# 11A-005.net
KiCad netlist of a schematic drawn in EAGLE
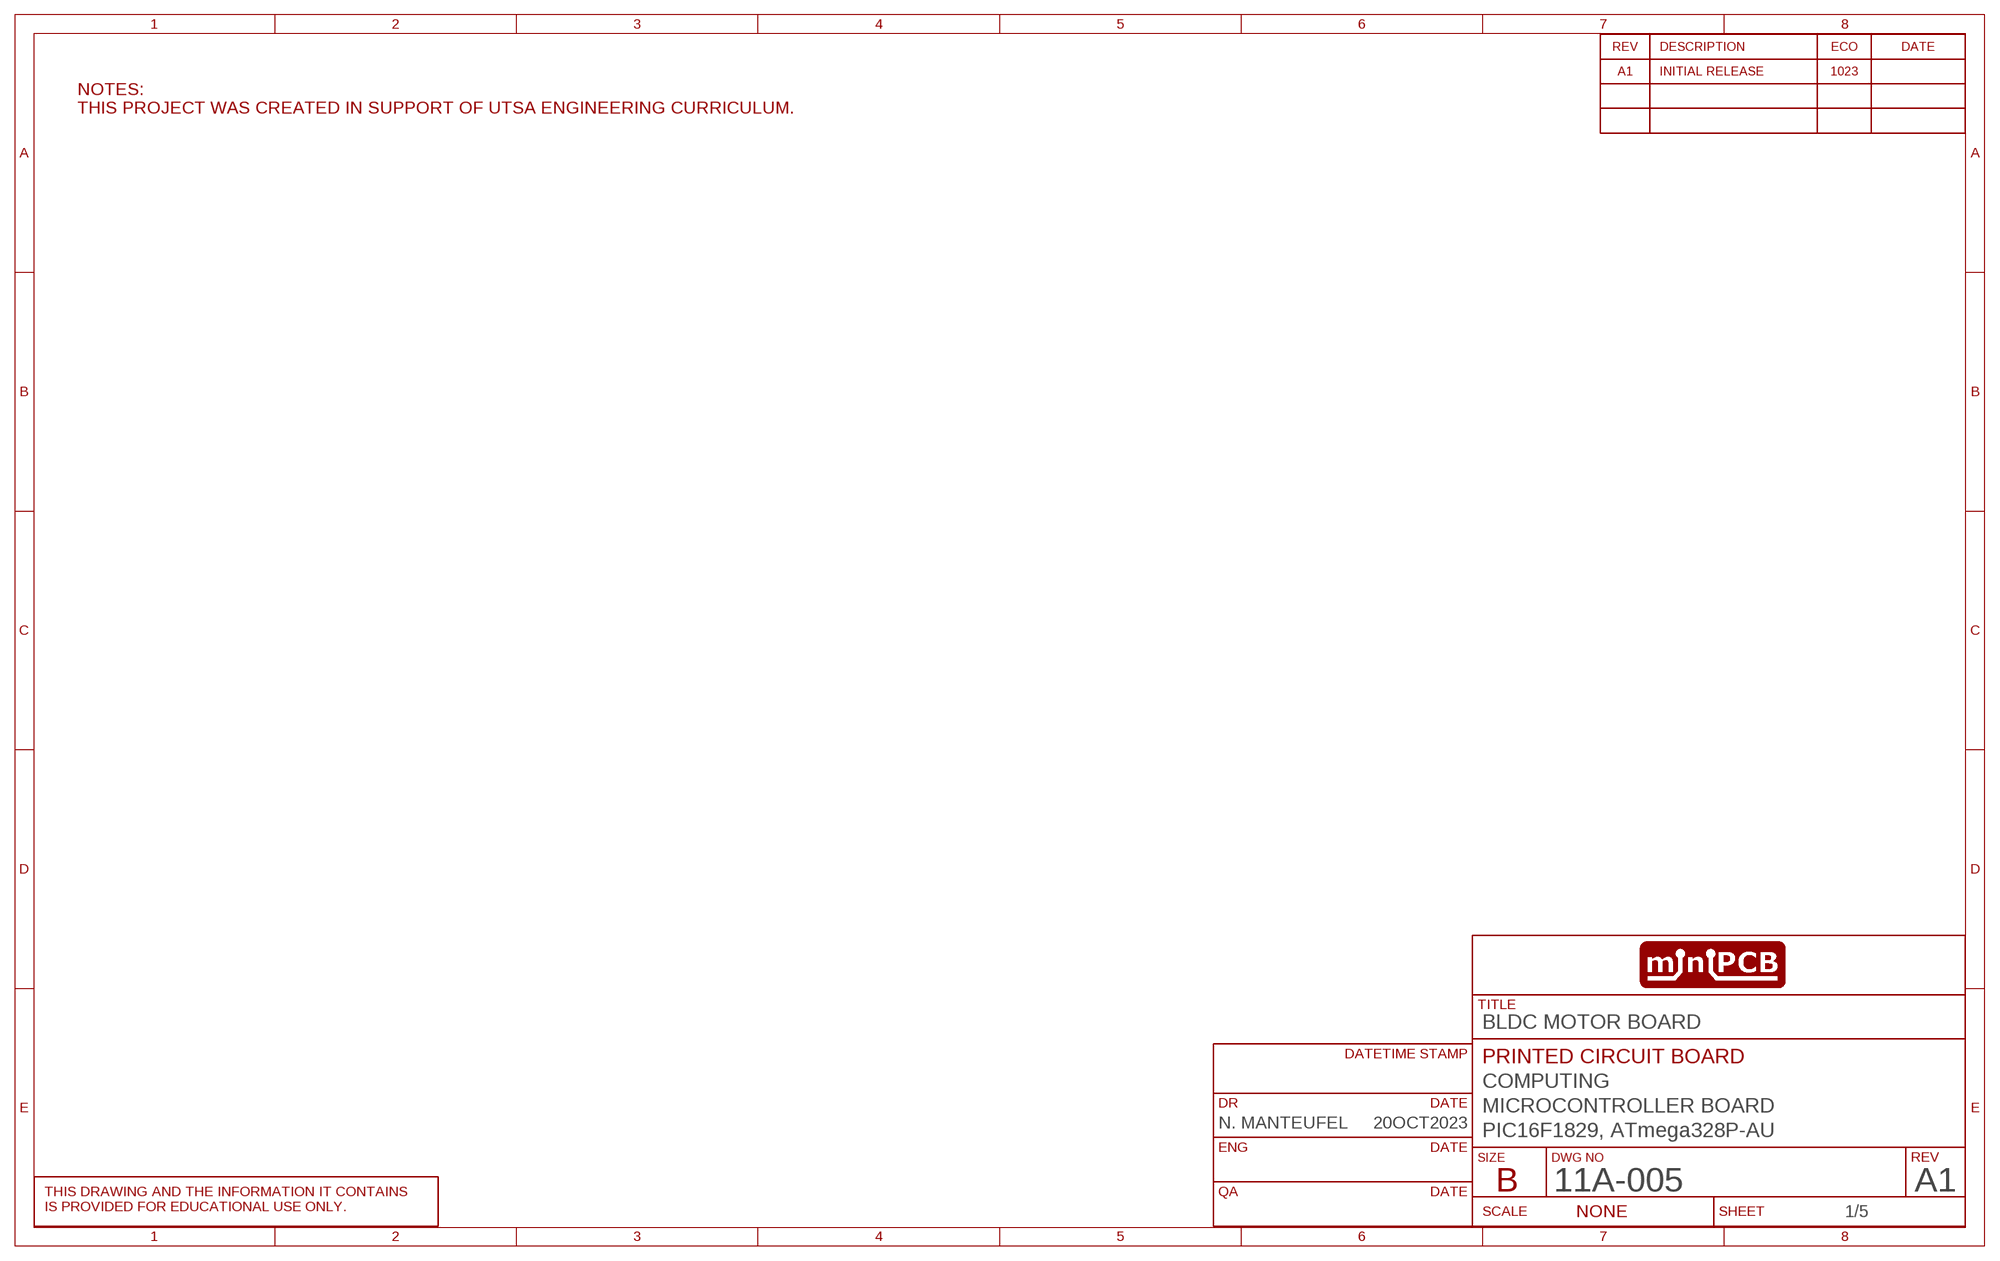
[diagram p0: schematic, sheet 1]
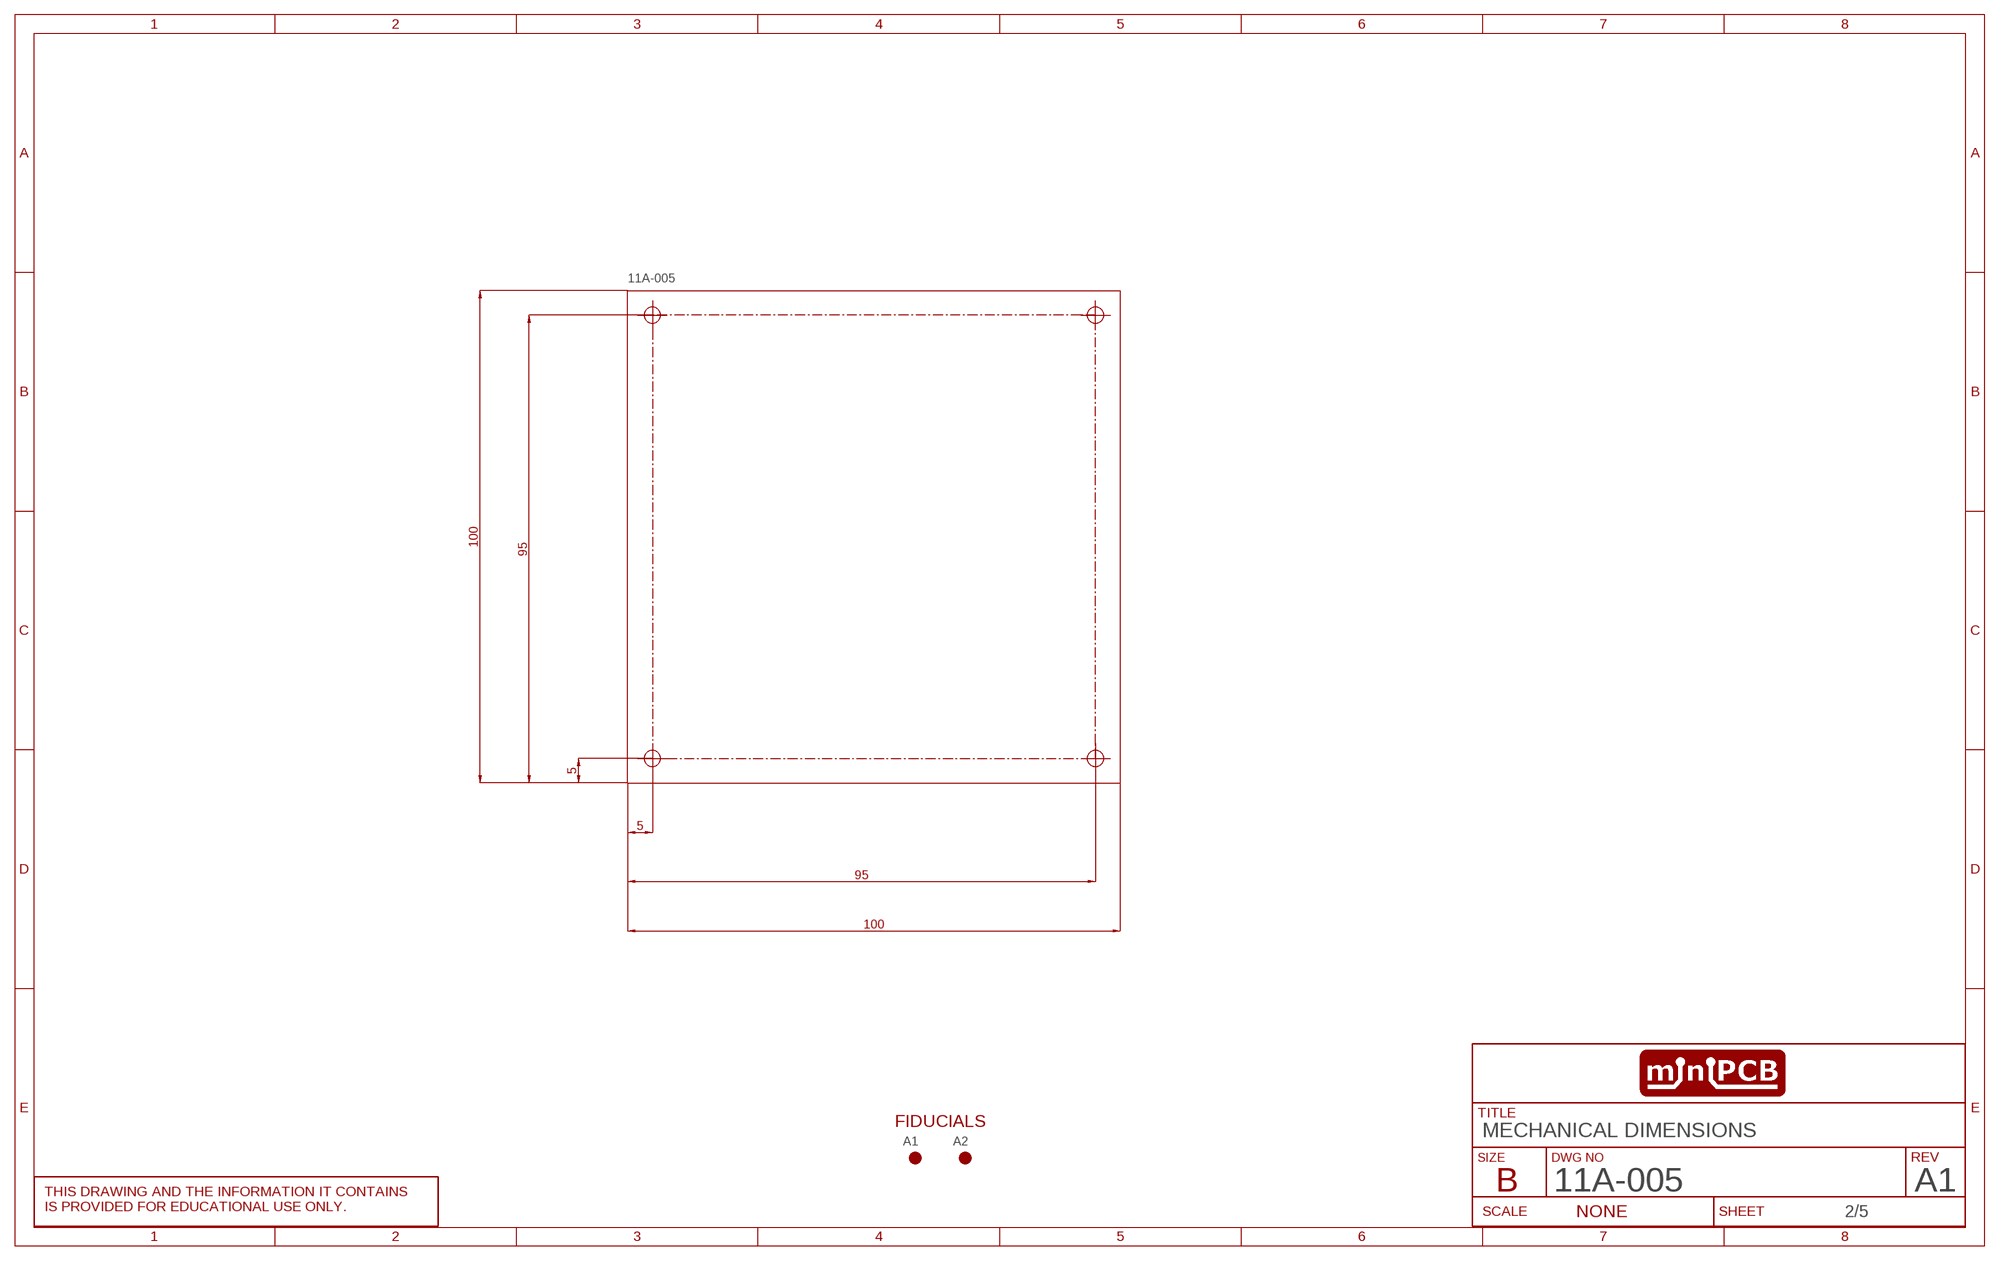
[diagram p1: schematic, sheet 2]
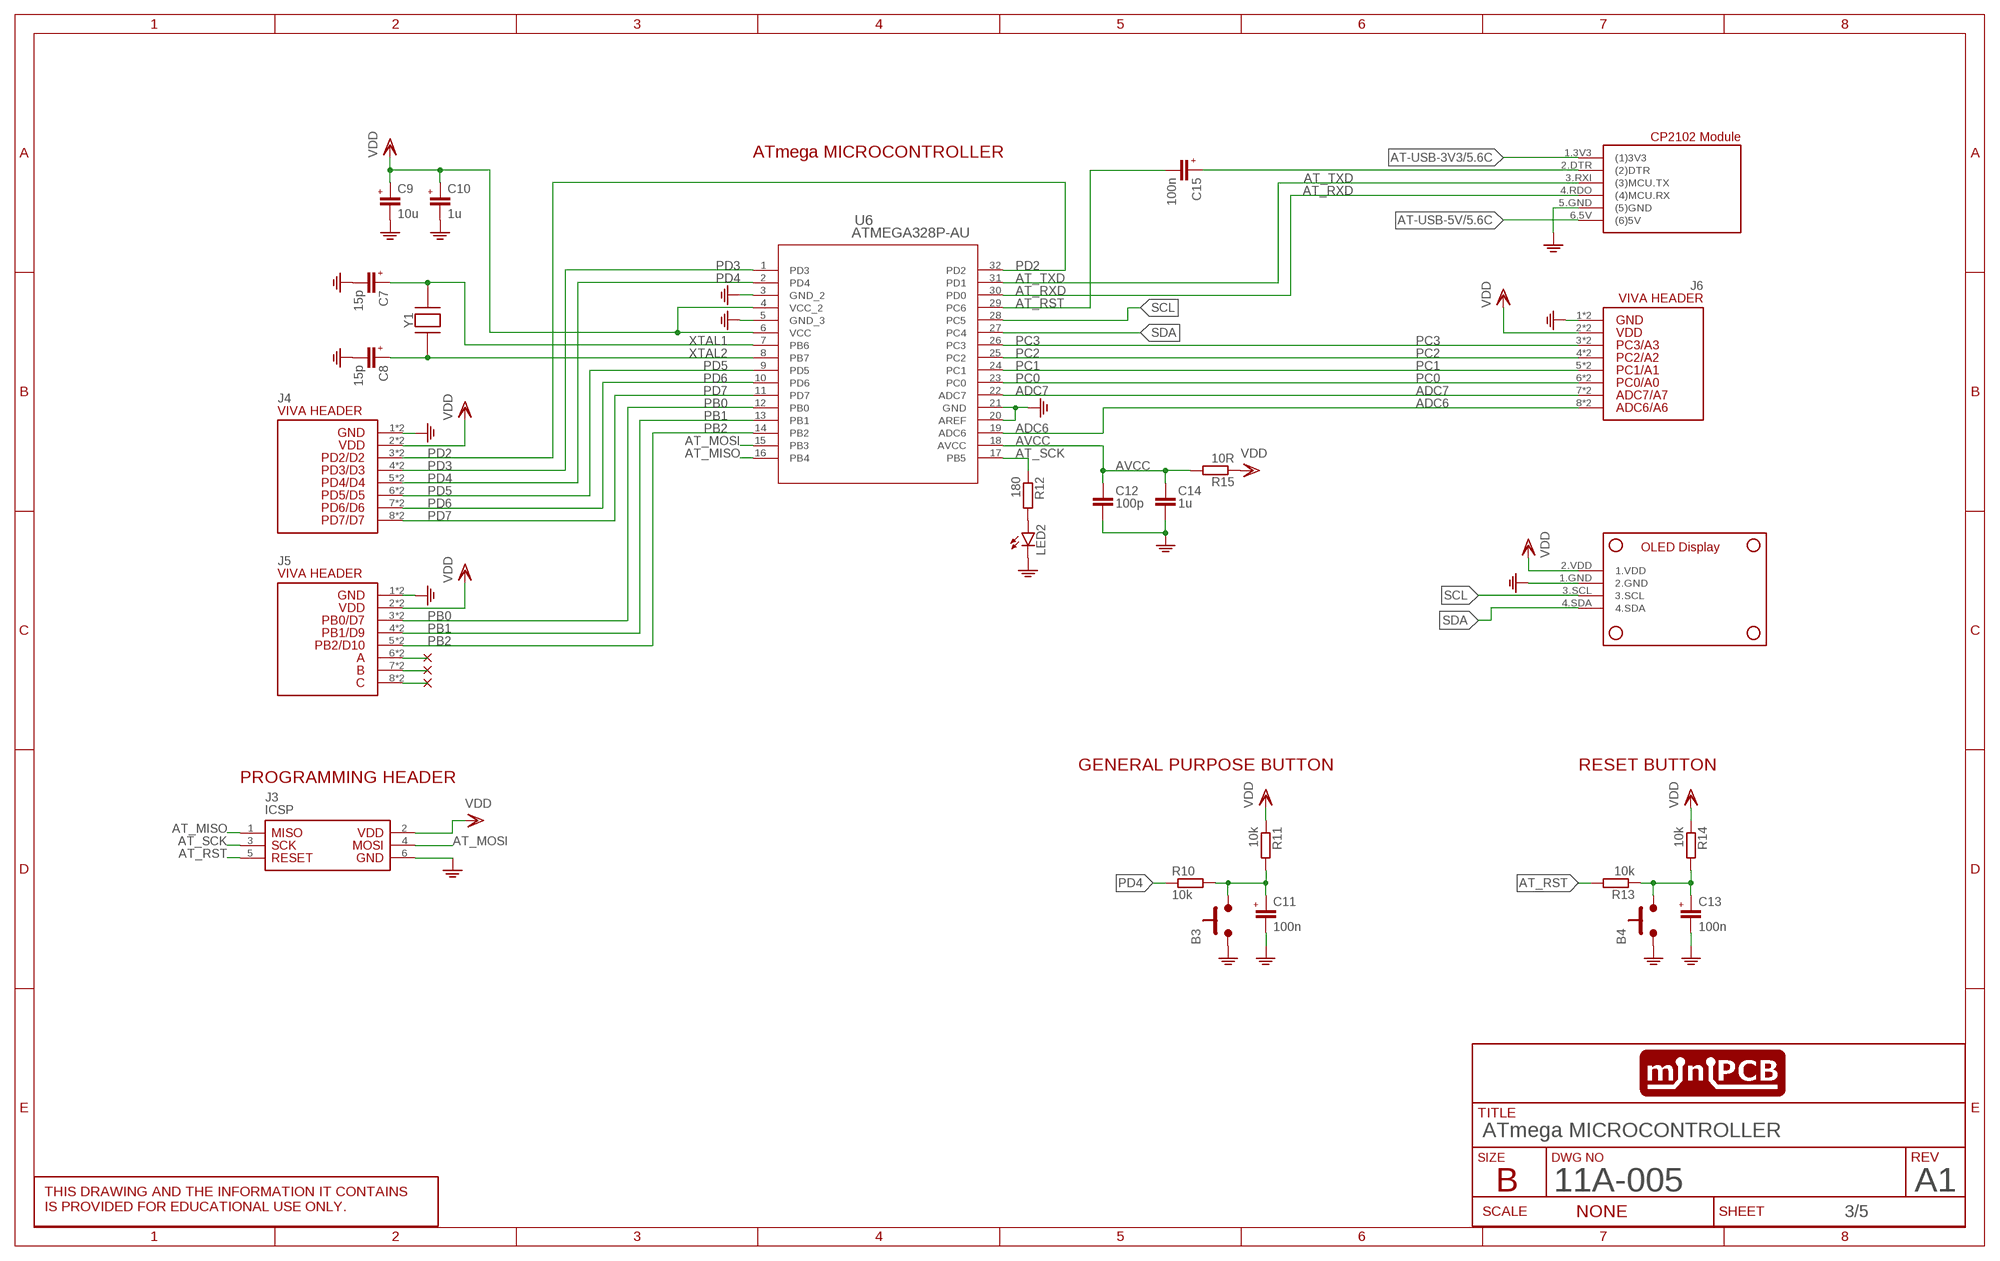
[diagram p2: schematic, sheet 3]
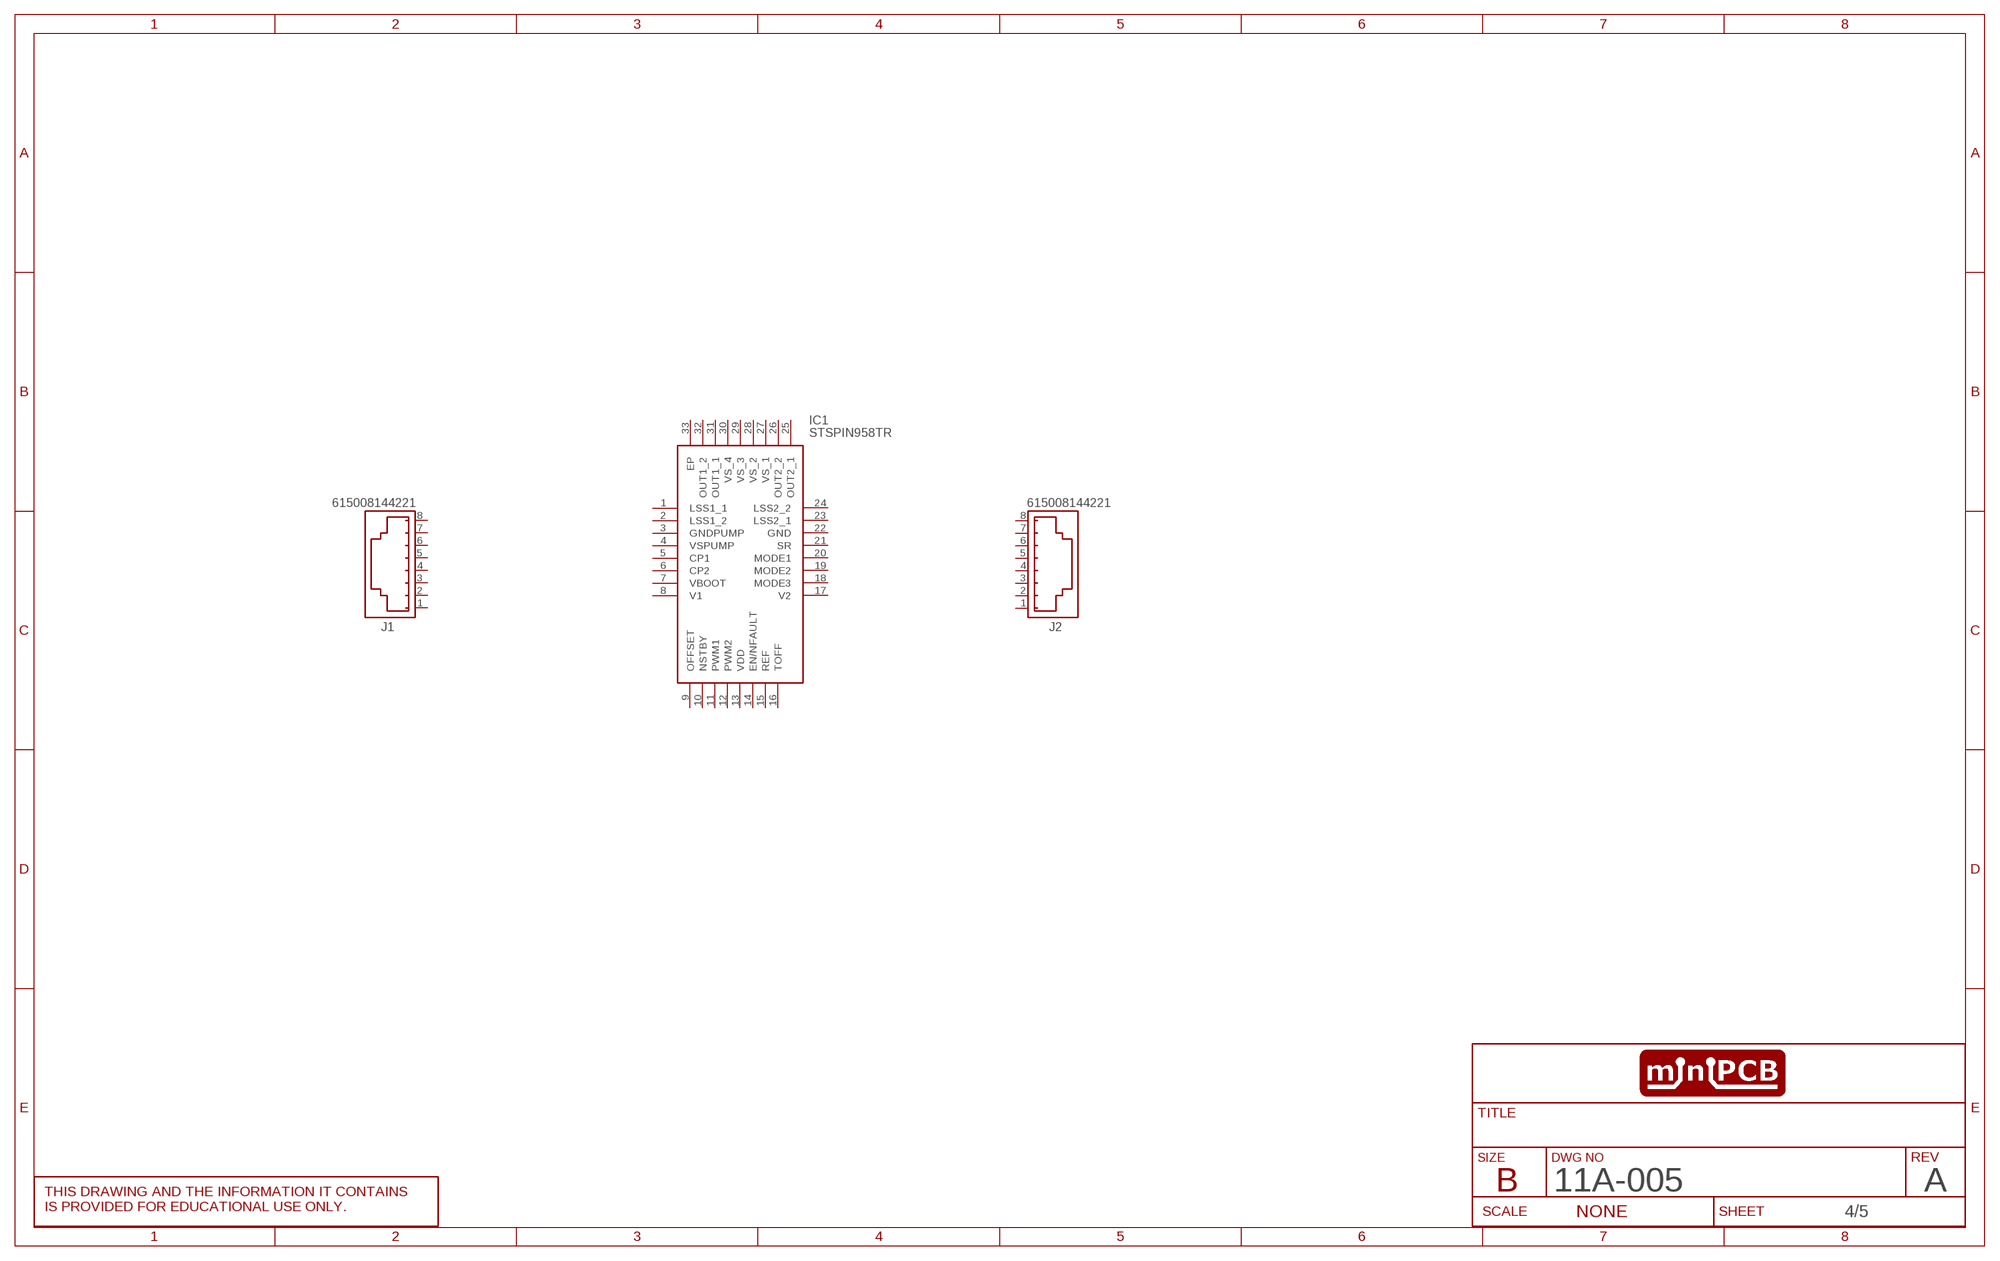
[diagram p3: schematic, sheet 4]
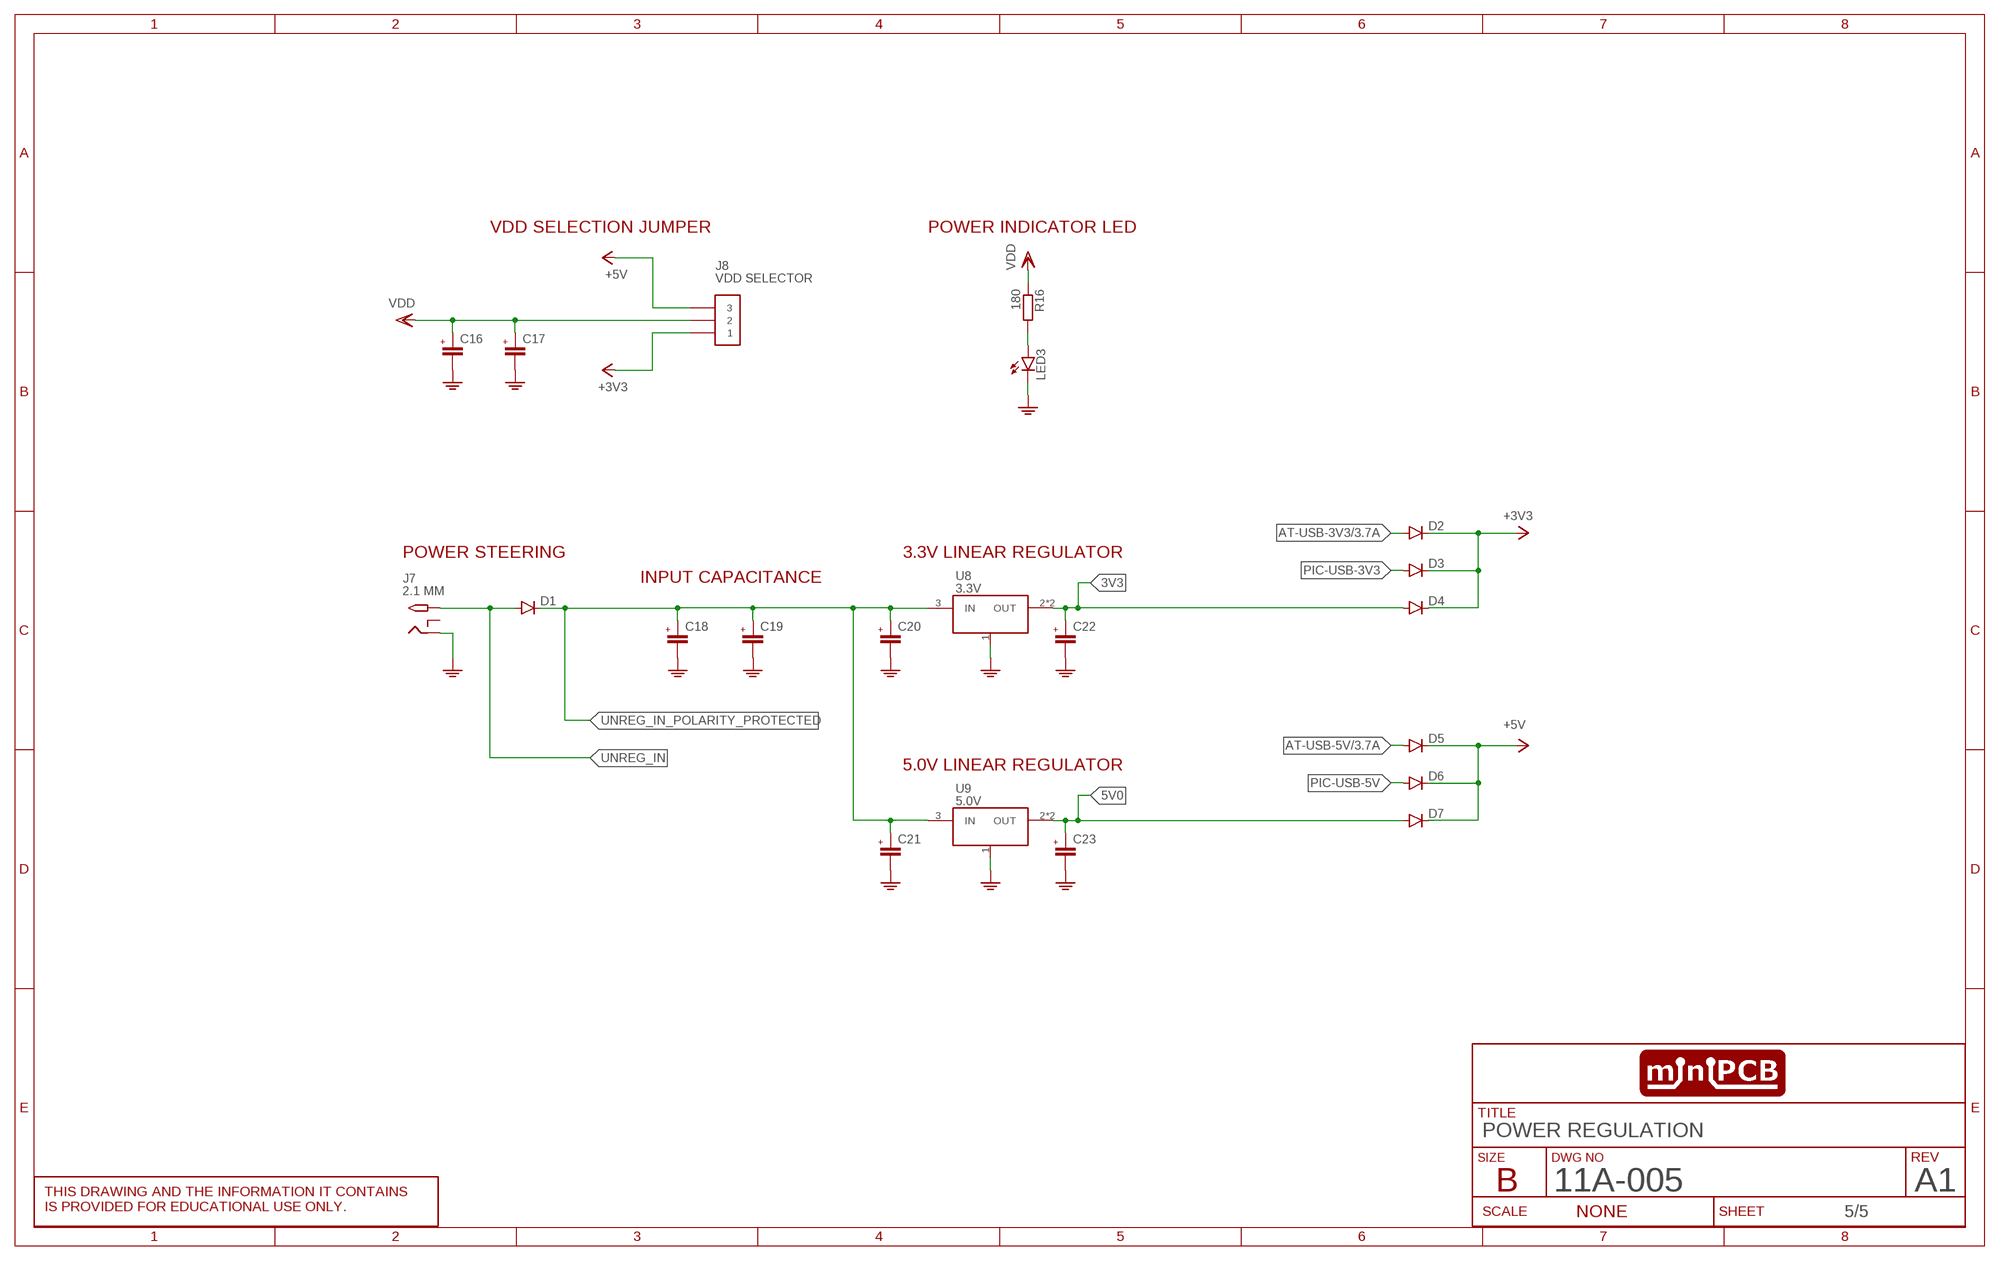
[diagram p4: schematic, sheet 5]

(export (version "E")
  (design (tool "Eeschema 10.0.6"))
  (components
    (comp (ref "IC1")
      (value "STSPIN958TR")
      (footprint "eagle-import:QFN50P500X500X100-33N")
      (fields (field (name "MOUSER_PART_NUMBER") "511-STSPIN958TR"))
      (libsource (lib "eagle-import") (part "STSPIN958TR"))
    )
    (comp (ref "J1")
      (value "615008144221")
      (footprint "eagle-import:615008144221")
      (libsource (lib "eagle-import") (part "615008144221"))
    )
    (comp (ref "J2")
      (value "615008144221")
      (footprint "eagle-import:615008144221")
      (libsource (lib "eagle-import") (part "615008144221"))
    )
    (comp (ref "$3_73_$")
      (value "VIVA_OLEDGND")
      (footprint "eagle-import:VIVA_OLED-I2C-ALT")
      (libsource (lib "eagle-import") (part "VIVA_OLEDGND"))
    )
    (comp (ref "B3")
      (value "PUSHBUTTON6X6MM")
      (footprint "eagle-import:6X6MM")
      (libsource (lib "eagle-import") (part "PUSHBUTTON6X6MM"))
    )
    (comp (ref "B4")
      (value "PUSHBUTTON6X6MM")
      (footprint "eagle-import:6X6MM")
      (libsource (lib "eagle-import") (part "PUSHBUTTON6X6MM"))
    )
    (comp (ref "C7")
      (value "15p")
      (footprint "eagle-import:C0603")
      (libsource (lib "eagle-import") (part "C0603"))
    )
    (comp (ref "C8")
      (value "15p")
      (footprint "eagle-import:C0603")
      (libsource (lib "eagle-import") (part "C0603"))
    )
    (comp (ref "C9")
      (value "10u")
      (footprint "eagle-import:C0805")
      (libsource (lib "eagle-import") (part "C0805"))
    )
    (comp (ref "C10")
      (value "1u")
      (footprint "eagle-import:C0805")
      (libsource (lib "eagle-import") (part "C0805"))
    )
    (comp (ref "C11")
      (value "100n")
      (footprint "eagle-import:C0805")
      (libsource (lib "eagle-import") (part "C0805"))
    )
    (comp (ref "C12")
      (value "100p")
      (footprint "eagle-import:C0805")
      (libsource (lib "eagle-import") (part "C-EU_C0805"))
    )
    (comp (ref "C13")
      (value "100n")
      (footprint "eagle-import:C0805")
      (libsource (lib "eagle-import") (part "C0805"))
    )
    (comp (ref "C14")
      (value "1u")
      (footprint "eagle-import:C0805")
      (libsource (lib "eagle-import") (part "C-EU_C0805"))
    )
    (comp (ref "C15")
      (value "100n")
      (footprint "eagle-import:C0805")
      (libsource (lib "eagle-import") (part "C0805"))
    )
    (comp (ref "J3")
      (value "ICSP")
      (footprint "eagle-import:PINS_6-2X3_AT")
      (fields
        (field (name "P1") "P1 NAME")
        (field (name "P3") "P3 NAME")
        (field (name "P5") "P5 NAME")
        (field (name "P2") "P2 NAME")
        (field (name "P4") "P4 NAME")
        (field (name "P6") "P6 NAME")
        (field (name "P1_1") "MISO")
        (field (name "P2_1") "VDD")
        (field (name "P3_1") "SCK")
        (field (name "P4_1") "MOSI")
        (field (name "P5_1") "RESET")
        (field (name "P6_1") "GND")
      )
      (libsource (lib "eagle-import") (part "PINS_6-2X3_AT"))
    )
    (comp (ref "J4")
      (value "VIVA-HEADER-ADC-8P")
      (footprint "eagle-import:VIVA-HEADER-ADC-8P")
      (fields
        (field (name "P3") "P3 TEXT")
        (field (name "P4") "P4 TEXT")
        (field (name "P5") "P5 TEXT")
        (field (name "P6") "P6 TEXT")
        (field (name "P7") "P7 TEXT")
        (field (name "P8") "P8 TEXT")
        (field (name "P3_1") "PD2/D2")
        (field (name "P4_1") "PD3/D3")
        (field (name "P5_1") "PD4/D4")
        (field (name "P6_1") "PD5/D5")
        (field (name "P7_1") "PD6/D6")
        (field (name "P8_1") "PD7/D7")
      )
      (libsource (lib "eagle-import") (part "VIVA-HEADER-ADC-8P"))
    )
    (comp (ref "J5")
      (value "VIVA-HEADER-ADC-8P")
      (footprint "eagle-import:VIVA-HEADER-ADC-8P")
      (fields
        (field (name "P3") "P3 TEXT")
        (field (name "P4") "P4 TEXT")
        (field (name "P5") "P5 TEXT")
        (field (name "P6") "P6 TEXT")
        (field (name "P7") "P7 TEXT")
        (field (name "P8") "P8 TEXT")
        (field (name "P3_1") "PB0/D7")
        (field (name "P4_1") "PB1/D9")
        (field (name "P5_1") "PB2/D10")
        (field (name "P6_1") "A")
        (field (name "P7_1") "B")
        (field (name "P8_1") "C")
      )
      (libsource (lib "eagle-import") (part "VIVA-HEADER-ADC-8P"))
    )
    (comp (ref "J6")
      (value "VIVA-HEADER-ADC-8P")
      (footprint "eagle-import:VIVA-HEADER-ADC-8P")
      (fields
        (field (name "P3") "P3 TEXT")
        (field (name "P4") "P4 TEXT")
        (field (name "P5") "P5 TEXT")
        (field (name "P6") "P6 TEXT")
        (field (name "P7") "P7 TEXT")
        (field (name "P8") "P8 TEXT")
        (field (name "P3_1") "PC3/A3")
        (field (name "P4_1") "PC2/A2")
        (field (name "P5_1") "PC1/A1")
        (field (name "P6_1") "PC0/A0")
        (field (name "P7_1") "ADC7/A7")
        (field (name "P8_1") "ADC6/A6")
      )
      (libsource (lib "eagle-import") (part "VIVA-HEADER-ADC-8P"))
    )
    (comp (ref "LED2")
      (value "LEDSML0805")
      (footprint "eagle-import:SML0805")
      (libsource (lib "eagle-import") (part "LEDSML0805"))
    )
    (comp (ref "R10")
      (value "10k")
      (footprint "eagle-import:R0805")
      (libsource (lib "eagle-import") (part "R-EU__R0805"))
    )
    (comp (ref "R11")
      (value "10k")
      (footprint "eagle-import:R0805")
      (libsource (lib "eagle-import") (part "R-EU__R0805"))
    )
    (comp (ref "R12")
      (value "180")
      (footprint "eagle-import:R0805")
      (libsource (lib "eagle-import") (part "R-EU__R0805"))
    )
    (comp (ref "R13")
      (value "10k")
      (footprint "eagle-import:R0805")
      (libsource (lib "eagle-import") (part "R-EU__R0805"))
    )
    (comp (ref "R14")
      (value "10k")
      (footprint "eagle-import:R0805")
      (libsource (lib "eagle-import") (part "R-EU__R0805"))
    )
    (comp (ref "R15")
      (value "10R")
      (footprint "eagle-import:R0805")
      (libsource (lib "eagle-import") (part "R-EU__R0805"))
    )
    (comp (ref "U6")
      (value "ATMEGA328P-AU")
      (footprint "eagle-import:32A_ATM")
      (fields
        (field (name "MANUFACTURER_PART_NUMBER") "ATMEGA328-AU")
        (field (name "COPYRIGHT") "Copyright (C) 2021 Ultra Librarian. All rights reserved.")
      )
      (libsource (lib "eagle-import") (part "ATMEGA328-AU"))
    )
    (comp (ref "U7")
      (value "VIVA_USB-TTL")
      (footprint "eagle-import:VIVA_USB_TTL_SUBTEXT")
      (libsource (lib "eagle-import") (part "VIVA_USB-TTL"))
    )
    (comp (ref "Y1")
      (value "CRYSTAL-3225_4P")
      (footprint "eagle-import:TXC7M2")
      (libsource (lib "eagle-import") (part "CRYSTAL-3225_4P"))
    )
    (comp (ref "-")
      (value "11A-005")
      (footprint "eagle-import:PCB_100X100")
      (libsource (lib "eagle-import") (part "PCB_100X100"))
    )
    (comp (ref "A1")
      (value "FIDUCIAL")
      (footprint "eagle-import:FIDUCIAL")
      (libsource (lib "eagle-import") (part "FIDUCIAL"))
    )
    (comp (ref "A2")
      (value "FIDUCIAL")
      (footprint "eagle-import:FIDUCIAL")
      (libsource (lib "eagle-import") (part "FIDUCIAL"))
    )
    (comp (ref "C16")
      (value "C0805")
      (footprint "eagle-import:C0805")
      (libsource (lib "eagle-import") (part "C0805"))
    )
    (comp (ref "C17")
      (value "C0805")
      (footprint "eagle-import:C0805")
      (libsource (lib "eagle-import") (part "C0805"))
    )
    (comp (ref "C18")
      (value "C0805")
      (footprint "eagle-import:C0805")
      (libsource (lib "eagle-import") (part "C0805"))
    )
    (comp (ref "C19")
      (value "C0805")
      (footprint "eagle-import:C0805")
      (libsource (lib "eagle-import") (part "C0805"))
    )
    (comp (ref "C20")
      (value "C0805")
      (footprint "eagle-import:C0805")
      (libsource (lib "eagle-import") (part "C0805"))
    )
    (comp (ref "C21")
      (value "C0805")
      (footprint "eagle-import:C0805")
      (libsource (lib "eagle-import") (part "C0805"))
    )
    (comp (ref "C22")
      (value "C0805")
      (footprint "eagle-import:C0805")
      (libsource (lib "eagle-import") (part "C0805"))
    )
    (comp (ref "C23")
      (value "C0805")
      (footprint "eagle-import:C0805")
      (libsource (lib "eagle-import") (part "C0805"))
    )
    (comp (ref "D1")
      (value "DIODE-DO214AC")
      (footprint "eagle-import:DO214AC")
      (libsource (lib "eagle-import") (part "DIODE-DO214AC"))
    )
    (comp (ref "D2")
      (value "DIODE-DO214AC")
      (footprint "eagle-import:DO214AC")
      (libsource (lib "eagle-import") (part "DIODE-DO214AC"))
    )
    (comp (ref "D3")
      (value "DIODE-DO214AC")
      (footprint "eagle-import:DO214AC")
      (libsource (lib "eagle-import") (part "DIODE-DO214AC"))
    )
    (comp (ref "D4")
      (value "DIODE-DO214AC")
      (footprint "eagle-import:DO214AC")
      (libsource (lib "eagle-import") (part "DIODE-DO214AC"))
    )
    (comp (ref "D5")
      (value "DIODE-DO214AC")
      (footprint "eagle-import:DO214AC")
      (libsource (lib "eagle-import") (part "DIODE-DO214AC"))
    )
    (comp (ref "D6")
      (value "DIODE-DO214AC")
      (footprint "eagle-import:DO214AC")
      (libsource (lib "eagle-import") (part "DIODE-DO214AC"))
    )
    (comp (ref "D7")
      (value "DIODE-DO214AC")
      (footprint "eagle-import:DO214AC")
      (libsource (lib "eagle-import") (part "DIODE-DO214AC"))
    )
    (comp (ref "J7")
      (value "2.1 MM")
      (footprint "eagle-import:PJ-102A")
      (libsource (lib "eagle-import") (part "2.1MMJACKTHM"))
    )
    (comp (ref "J8")
      (value "VDD SELECTOR")
      (footprint "eagle-import:PINS_3")
      (libsource (lib "eagle-import") (part "PINS_3_2.54"))
    )
    (comp (ref "LED3")
      (value "LEDSML0805")
      (footprint "eagle-import:SML0805")
      (libsource (lib "eagle-import") (part "LEDSML0805"))
    )
    (comp (ref "R16")
      (value "180")
      (footprint "eagle-import:R0805")
      (libsource (lib "eagle-import") (part "R-EU__R0805"))
    )
    (comp (ref "U8")
      (value "3.3V")
      (footprint "eagle-import:SOT223")
      (libsource (lib "eagle-import") (part "REGULATOR_SCHLM1117"))
    )
    (comp (ref "U9")
      (value "5.0V")
      (footprint "eagle-import:SOT223")
      (libsource (lib "eagle-import") (part "REGULATOR_SCHLM1117"))
    )
  )
  (nets
    (net (code "1") (name "+3V3") (class "Default")
      (node (ref "D2") (pin "C") (pinfunction "C_C") (pintype "passive"))
      (node (ref "D3") (pin "C") (pinfunction "C_C") (pintype "passive"))
      (node (ref "D4") (pin "C") (pinfunction "C_C") (pintype "passive"))
      (node (ref "J8") (pin "1") (pinfunction "1_1") (pintype "bidirectional"))
    )
    (net (code "2") (name "+5V") (class "Default")
      (node (ref "D5") (pin "C") (pinfunction "C_C") (pintype "passive"))
      (node (ref "D6") (pin "C") (pinfunction "C_C") (pintype "passive"))
      (node (ref "D7") (pin "C") (pinfunction "C_C") (pintype "passive"))
      (node (ref "J8") (pin "3") (pinfunction "3_3") (pintype "bidirectional"))
    )
    (net (code "3") (name "3V3") (class "Default")
      (node (ref "C22") (pin "1") (pinfunction "+_1") (pintype "passive"))
      (node (ref "D4") (pin "A") (pinfunction "A_A") (pintype "passive"))
      (node (ref "U8") (pin "2") (pinfunction "OUT_2") (pintype "bidirectional"))
      (node (ref "U8") (pin "4.TAB") (pinfunction "OUT_4.TAB") (pintype "bidirectional"))
    )
    (net (code "4") (name "5V0") (class "Default")
      (node (ref "C23") (pin "1") (pinfunction "+_1") (pintype "passive"))
      (node (ref "D7") (pin "A") (pinfunction "A_A") (pintype "passive"))
      (node (ref "U9") (pin "2") (pinfunction "OUT_2") (pintype "bidirectional"))
      (node (ref "U9") (pin "4.TAB") (pinfunction "OUT_4.TAB") (pintype "bidirectional"))
    )
    (net (code "5") (name "ADC6") (class "Default")
      (node (ref "J6") (pin "8") (pinfunction "8.ADC5_8") (pintype "bidirectional"))
      (node (ref "J6") (pin "9") (pinfunction "8.ADC5_9") (pintype "bidirectional"))
      (node (ref "U6") (pin "19") (pinfunction "ADC6_19") (pintype "passive"))
    )
    (net (code "6") (name "ADC7") (class "Default")
      (node (ref "J6") (pin "10") (pinfunction "7.ADC4_10") (pintype "bidirectional"))
      (node (ref "J6") (pin "7") (pinfunction "7.ADC4_7") (pintype "bidirectional"))
      (node (ref "U6") (pin "22") (pinfunction "ADC7_22") (pintype "passive"))
    )
    (net (code "7") (name "AT-USB-3V3") (class "Default")
      (node (ref "D2") (pin "A") (pinfunction "A_A") (pintype "passive"))
      (node (ref "U7") (pin "1.3V3") (pinfunction "(1)3V3_1.3V3") (pintype "bidirectional"))
    )
    (net (code "8") (name "AT-USB-5V") (class "Default")
      (node (ref "D5") (pin "A") (pinfunction "A_A") (pintype "passive"))
      (node (ref "U7") (pin "6.5V") (pinfunction "(6)5V_6.5V") (pintype "bidirectional"))
    )
    (net (code "9") (name "AT_MISO") (class "Default")
      (node (ref "J3") (pin "1") (pinfunction "1_1") (pintype "bidirectional"))
      (node (ref "U6") (pin "16") (pinfunction "PB4_16") (pintype "bidirectional"))
    )
    (net (code "10") (name "AT_MOSI") (class "Default")
      (node (ref "J3") (pin "4") (pinfunction "4_4") (pintype "bidirectional"))
      (node (ref "U6") (pin "15") (pinfunction "PB3_15") (pintype "bidirectional"))
    )
    (net (code "11") (name "AT_RST") (class "Default")
      (node (ref "C15") (pin "2") (pinfunction "-_2") (pintype "passive"))
      (node (ref "J3") (pin "5") (pinfunction "5_5") (pintype "bidirectional"))
      (node (ref "R13") (pin "2") (pinfunction "2_2") (pintype "passive"))
      (node (ref "U6") (pin "29") (pinfunction "PC6_29") (pintype "bidirectional"))
    )
    (net (code "12") (name "AT_RXD") (class "Default")
      (node (ref "U6") (pin "30") (pinfunction "PD0_30") (pintype "bidirectional"))
      (node (ref "U7") (pin "4.RDO") (pinfunction "(4)MCU.RX_4.RDO") (pintype "bidirectional"))
    )
    (net (code "13") (name "AT_SCK") (class "Default")
      (node (ref "J3") (pin "3") (pinfunction "3_3") (pintype "bidirectional"))
      (node (ref "R12") (pin "1") (pinfunction "1_1") (pintype "passive"))
      (node (ref "U6") (pin "17") (pinfunction "PB5_17") (pintype "bidirectional"))
    )
    (net (code "14") (name "AT_TXD") (class "Default")
      (node (ref "U6") (pin "31") (pinfunction "PD1_31") (pintype "bidirectional"))
      (node (ref "U7") (pin "3.RXI") (pinfunction "(3)MCU.TX_3.RXI") (pintype "bidirectional"))
    )
    (net (code "15") (name "AVCC") (class "Default")
      (node (ref "C12") (pin "1") (pinfunction "1_1") (pintype "passive"))
      (node (ref "C14") (pin "1") (pinfunction "1_1") (pintype "passive"))
      (node (ref "R15") (pin "2") (pinfunction "2_2") (pintype "passive"))
      (node (ref "U6") (pin "18") (pinfunction "AVCC_18") (pintype "power_in"))
    )
    (net (code "16") (name "GND") (class "Default")
      (node (ref "$3_73_$") (pin "1.GND") (pinfunction "2.GND_1.GND") (pintype "bidirectional"))
      (node (ref "B3") (pin "1.A") (pinfunction "1_1.A") (pintype "bidirectional"))
      (node (ref "B3") (pin "2.A") (pinfunction "1_2.A") (pintype "bidirectional"))
      (node (ref "B4") (pin "1.A") (pinfunction "1_1.A") (pintype "bidirectional"))
      (node (ref "B4") (pin "2.A") (pinfunction "1_2.A") (pintype "bidirectional"))
      (node (ref "C10") (pin "2") (pinfunction "-_2") (pintype "passive"))
      (node (ref "C11") (pin "2") (pinfunction "-_2") (pintype "passive"))
      (node (ref "C12") (pin "2") (pinfunction "2_2") (pintype "passive"))
      (node (ref "C13") (pin "2") (pinfunction "-_2") (pintype "passive"))
      (node (ref "C14") (pin "2") (pinfunction "2_2") (pintype "passive"))
      (node (ref "C16") (pin "2") (pinfunction "-_2") (pintype "passive"))
      (node (ref "C17") (pin "2") (pinfunction "-_2") (pintype "passive"))
      (node (ref "C18") (pin "2") (pinfunction "-_2") (pintype "passive"))
      (node (ref "C19") (pin "2") (pinfunction "-_2") (pintype "passive"))
      (node (ref "C20") (pin "2") (pinfunction "-_2") (pintype "passive"))
      (node (ref "C21") (pin "2") (pinfunction "-_2") (pintype "passive"))
      (node (ref "C22") (pin "2") (pinfunction "-_2") (pintype "passive"))
      (node (ref "C23") (pin "2") (pinfunction "-_2") (pintype "passive"))
      (node (ref "C7") (pin "1") (pinfunction "-_1") (pintype "passive"))
      (node (ref "C8") (pin "1") (pinfunction "-_1") (pintype "passive"))
      (node (ref "C9") (pin "2") (pinfunction "-_2") (pintype "passive"))
      (node (ref "J3") (pin "6") (pinfunction "6_6") (pintype "bidirectional"))
      (node (ref "J4") (pin "1") (pinfunction "1.GND_1") (pintype "bidirectional"))
      (node (ref "J4") (pin "16") (pinfunction "1.GND_16") (pintype "bidirectional"))
      (node (ref "J5") (pin "1") (pinfunction "1.GND_1") (pintype "bidirectional"))
      (node (ref "J5") (pin "16") (pinfunction "1.GND_16") (pintype "bidirectional"))
      (node (ref "J6") (pin "1") (pinfunction "1.GND_1") (pintype "bidirectional"))
      (node (ref "J6") (pin "16") (pinfunction "1.GND_16") (pintype "bidirectional"))
      (node (ref "J7") (pin "RING") (pinfunction "RING_RING") (pintype "bidirectional"))
      (node (ref "LED2") (pin "C") (pinfunction "C_C") (pintype "passive"))
      (node (ref "LED3") (pin "C") (pinfunction "C_C") (pintype "passive"))
      (node (ref "U6") (pin "20") (pinfunction "AREF_20") (pintype "passive"))
      (node (ref "U6") (pin "21") (pinfunction "GND_21") (pintype "power_in"))
      (node (ref "U6") (pin "3") (pinfunction "GND_2_3") (pintype "power_in"))
      (node (ref "U6") (pin "5") (pinfunction "GND_3_5") (pintype "power_in"))
      (node (ref "U7") (pin "5.GND") (pinfunction "(5)GND_5.GND") (pintype "bidirectional"))
      (node (ref "U8") (pin "1") (pinfunction "GND_1") (pintype "bidirectional"))
      (node (ref "U9") (pin "1") (pinfunction "GND_1") (pintype "bidirectional"))
    )
    (net (code "17") (name "Net-(C11-+)") (class "Default")
      (node (ref "B3") (pin "3.B") (pinfunction "2_3.B") (pintype "bidirectional"))
      (node (ref "B3") (pin "4.B") (pinfunction "2_4.B") (pintype "bidirectional"))
      (node (ref "C11") (pin "1") (pinfunction "+_1") (pintype "passive"))
      (node (ref "R10") (pin "2") (pinfunction "2_2") (pintype "passive"))
      (node (ref "R11") (pin "2") (pinfunction "2_2") (pintype "passive"))
    )
    (net (code "18") (name "Net-(C13-+)") (class "Default")
      (node (ref "B4") (pin "3.B") (pinfunction "2_3.B") (pintype "bidirectional"))
      (node (ref "B4") (pin "4.B") (pinfunction "2_4.B") (pintype "bidirectional"))
      (node (ref "C13") (pin "1") (pinfunction "+_1") (pintype "passive"))
      (node (ref "R13") (pin "1") (pinfunction "1_1") (pintype "passive"))
      (node (ref "R14") (pin "2") (pinfunction "2_2") (pintype "passive"))
    )
    (net (code "19") (name "Net-(C15-+)") (class "Default")
      (node (ref "C15") (pin "1") (pinfunction "+_1") (pintype "passive"))
      (node (ref "U7") (pin "2.DTR") (pinfunction "(2)DTR_2.DTR") (pintype "bidirectional"))
    )
    (net (code "20") (name "Net-(J5-6.ADC3-Pad11)") (class "Default")
      (node (ref "J5") (pin "11") (pinfunction "6.ADC3_11") (pintype "bidirectional"))
      (node (ref "J5") (pin "6") (pinfunction "6.ADC3_6") (pintype "bidirectional"))
    )
    (net (code "21") (name "Net-(J5-7.ADC4-Pad10)") (class "Default")
      (node (ref "J5") (pin "10") (pinfunction "7.ADC4_10") (pintype "bidirectional"))
      (node (ref "J5") (pin "7") (pinfunction "7.ADC4_7") (pintype "bidirectional"))
    )
    (net (code "22") (name "Net-(J5-8.ADC5-Pad8)") (class "Default")
      (node (ref "J5") (pin "8") (pinfunction "8.ADC5_8") (pintype "bidirectional"))
      (node (ref "J5") (pin "9") (pinfunction "8.ADC5_9") (pintype "bidirectional"))
    )
    (net (code "23") (name "Net-(LED2-PadA)") (class "Default")
      (node (ref "LED2") (pin "A") (pinfunction "A_A") (pintype "passive"))
      (node (ref "R12") (pin "2") (pinfunction "2_2") (pintype "passive"))
    )
    (net (code "24") (name "Net-(LED3-PadA)") (class "Default")
      (node (ref "LED3") (pin "A") (pinfunction "A_A") (pintype "passive"))
      (node (ref "R16") (pin "2") (pinfunction "2_2") (pintype "passive"))
    )
    (net (code "25") (name "PB0") (class "Default")
      (node (ref "J5") (pin "14") (pinfunction "3.ADC0_14") (pintype "bidirectional"))
      (node (ref "J5") (pin "3") (pinfunction "3.ADC0_3") (pintype "bidirectional"))
      (node (ref "U6") (pin "12") (pinfunction "PB0_12") (pintype "bidirectional"))
    )
    (net (code "26") (name "PB1") (class "Default")
      (node (ref "J5") (pin "13") (pinfunction "4.ADC1_13") (pintype "bidirectional"))
      (node (ref "J5") (pin "4") (pinfunction "4.ADC1_4") (pintype "bidirectional"))
      (node (ref "U6") (pin "13") (pinfunction "PB1_13") (pintype "bidirectional"))
    )
    (net (code "27") (name "PB2") (class "Default")
      (node (ref "J5") (pin "12") (pinfunction "5.ADC2_12") (pintype "bidirectional"))
      (node (ref "J5") (pin "5") (pinfunction "5.ADC2_5") (pintype "bidirectional"))
      (node (ref "U6") (pin "14") (pinfunction "PB2_14") (pintype "bidirectional"))
    )
    (net (code "28") (name "PC0") (class "Default")
      (node (ref "J6") (pin "11") (pinfunction "6.ADC3_11") (pintype "bidirectional"))
      (node (ref "J6") (pin "6") (pinfunction "6.ADC3_6") (pintype "bidirectional"))
      (node (ref "U6") (pin "23") (pinfunction "PC0_23") (pintype "bidirectional"))
    )
    (net (code "29") (name "PC1") (class "Default")
      (node (ref "J6") (pin "12") (pinfunction "5.ADC2_12") (pintype "bidirectional"))
      (node (ref "J6") (pin "5") (pinfunction "5.ADC2_5") (pintype "bidirectional"))
      (node (ref "U6") (pin "24") (pinfunction "PC1_24") (pintype "bidirectional"))
    )
    (net (code "30") (name "PC2") (class "Default")
      (node (ref "J6") (pin "13") (pinfunction "4.ADC1_13") (pintype "bidirectional"))
      (node (ref "J6") (pin "4") (pinfunction "4.ADC1_4") (pintype "bidirectional"))
      (node (ref "U6") (pin "25") (pinfunction "PC2_25") (pintype "bidirectional"))
    )
    (net (code "31") (name "PC3") (class "Default")
      (node (ref "J6") (pin "14") (pinfunction "3.ADC0_14") (pintype "bidirectional"))
      (node (ref "J6") (pin "3") (pinfunction "3.ADC0_3") (pintype "bidirectional"))
      (node (ref "U6") (pin "26") (pinfunction "PC3_26") (pintype "bidirectional"))
    )
    (net (code "32") (name "PD2") (class "Default")
      (node (ref "J4") (pin "14") (pinfunction "3.ADC0_14") (pintype "bidirectional"))
      (node (ref "J4") (pin "3") (pinfunction "3.ADC0_3") (pintype "bidirectional"))
      (node (ref "U6") (pin "32") (pinfunction "PD2_32") (pintype "bidirectional"))
    )
    (net (code "33") (name "PD3") (class "Default")
      (node (ref "J4") (pin "13") (pinfunction "4.ADC1_13") (pintype "bidirectional"))
      (node (ref "J4") (pin "4") (pinfunction "4.ADC1_4") (pintype "bidirectional"))
      (node (ref "U6") (pin "1") (pinfunction "PD3_1") (pintype "bidirectional"))
    )
    (net (code "34") (name "PD4") (class "Default")
      (node (ref "J4") (pin "12") (pinfunction "5.ADC2_12") (pintype "bidirectional"))
      (node (ref "J4") (pin "5") (pinfunction "5.ADC2_5") (pintype "bidirectional"))
      (node (ref "R10") (pin "1") (pinfunction "1_1") (pintype "passive"))
      (node (ref "U6") (pin "2") (pinfunction "PD4_2") (pintype "bidirectional"))
    )
    (net (code "35") (name "PD5") (class "Default")
      (node (ref "J4") (pin "11") (pinfunction "6.ADC3_11") (pintype "bidirectional"))
      (node (ref "J4") (pin "6") (pinfunction "6.ADC3_6") (pintype "bidirectional"))
      (node (ref "U6") (pin "9") (pinfunction "PD5_9") (pintype "bidirectional"))
    )
    (net (code "36") (name "PD6") (class "Default")
      (node (ref "J4") (pin "10") (pinfunction "7.ADC4_10") (pintype "bidirectional"))
      (node (ref "J4") (pin "7") (pinfunction "7.ADC4_7") (pintype "bidirectional"))
      (node (ref "U6") (pin "10") (pinfunction "PD6_10") (pintype "bidirectional"))
    )
    (net (code "37") (name "PD7") (class "Default")
      (node (ref "J4") (pin "8") (pinfunction "8.ADC5_8") (pintype "bidirectional"))
      (node (ref "J4") (pin "9") (pinfunction "8.ADC5_9") (pintype "bidirectional"))
      (node (ref "U6") (pin "11") (pinfunction "PD7_11") (pintype "bidirectional"))
    )
    (net (code "38") (name "PIC-USB-3V3") (class "Default")
      (node (ref "D3") (pin "A") (pinfunction "A_A") (pintype "passive"))
    )
    (net (code "39") (name "PIC-USB-5V") (class "Default")
      (node (ref "D6") (pin "A") (pinfunction "A_A") (pintype "passive"))
    )
    (net (code "40") (name "SCL") (class "Default")
      (node (ref "$3_73_$") (pin "3.SCL") (pinfunction "3.SCL_3.SCL") (pintype "bidirectional"))
      (node (ref "U6") (pin "28") (pinfunction "PC5_28") (pintype "bidirectional"))
    )
    (net (code "41") (name "SDA") (class "Default")
      (node (ref "$3_73_$") (pin "4.SDA") (pinfunction "4.SDA_4.SDA") (pintype "bidirectional"))
      (node (ref "U6") (pin "27") (pinfunction "PC4_27") (pintype "bidirectional"))
    )
    (net (code "42") (name "UNREG_IN") (class "Default")
      (node (ref "D1") (pin "A") (pinfunction "A_A") (pintype "passive"))
      (node (ref "J7") (pin "TIP") (pinfunction "TIP_TIP") (pintype "bidirectional"))
    )
    (net (code "43") (name "UNREG_IN_POLARITY_PROTECTED") (class "Default")
      (node (ref "C18") (pin "1") (pinfunction "+_1") (pintype "passive"))
      (node (ref "C19") (pin "1") (pinfunction "+_1") (pintype "passive"))
      (node (ref "C20") (pin "1") (pinfunction "+_1") (pintype "passive"))
      (node (ref "C21") (pin "1") (pinfunction "+_1") (pintype "passive"))
      (node (ref "D1") (pin "C") (pinfunction "C_C") (pintype "passive"))
      (node (ref "U8") (pin "3") (pinfunction "IN_3") (pintype "bidirectional"))
      (node (ref "U9") (pin "3") (pinfunction "IN_3") (pintype "bidirectional"))
    )
    (net (code "44") (name "VDD") (class "Default")
      (node (ref "$3_73_$") (pin "2.VDD") (pinfunction "1.VDD_2.VDD") (pintype "bidirectional"))
      (node (ref "C10") (pin "1") (pinfunction "+_1") (pintype "passive"))
      (node (ref "C16") (pin "1") (pinfunction "+_1") (pintype "passive"))
      (node (ref "C17") (pin "1") (pinfunction "+_1") (pintype "passive"))
      (node (ref "C9") (pin "1") (pinfunction "+_1") (pintype "passive"))
      (node (ref "J3") (pin "2") (pinfunction "2_2") (pintype "bidirectional"))
      (node (ref "J4") (pin "15") (pinfunction "2.VDD_15") (pintype "bidirectional"))
      (node (ref "J4") (pin "2") (pinfunction "2.VDD_2") (pintype "bidirectional"))
      (node (ref "J5") (pin "15") (pinfunction "2.VDD_15") (pintype "bidirectional"))
      (node (ref "J5") (pin "2") (pinfunction "2.VDD_2") (pintype "bidirectional"))
      (node (ref "J6") (pin "15") (pinfunction "2.VDD_15") (pintype "bidirectional"))
      (node (ref "J6") (pin "2") (pinfunction "2.VDD_2") (pintype "bidirectional"))
      (node (ref "J8") (pin "2") (pinfunction "2_2") (pintype "bidirectional"))
      (node (ref "R11") (pin "1") (pinfunction "1_1") (pintype "passive"))
      (node (ref "R14") (pin "1") (pinfunction "1_1") (pintype "passive"))
      (node (ref "R15") (pin "1") (pinfunction "1_1") (pintype "passive"))
      (node (ref "R16") (pin "1") (pinfunction "1_1") (pintype "passive"))
      (node (ref "U6") (pin "4") (pinfunction "VCC_2_4") (pintype "power_in"))
      (node (ref "U6") (pin "6") (pinfunction "VCC_6") (pintype "power_in"))
    )
    (net (code "45") (name "XTAL1") (class "Default")
      (node (ref "C7") (pin "2") (pinfunction "+_2") (pintype "passive"))
      (node (ref "U6") (pin "7") (pinfunction "PB6_7") (pintype "bidirectional"))
      (node (ref "Y1") (pin "3") (pinfunction "2_3") (pintype "bidirectional"))
    )
    (net (code "46") (name "XTAL2") (class "Default")
      (node (ref "C8") (pin "2") (pinfunction "+_2") (pintype "passive"))
      (node (ref "U6") (pin "8") (pinfunction "PB7_8") (pintype "bidirectional"))
      (node (ref "Y1") (pin "1") (pinfunction "1_1") (pintype "bidirectional"))
    )
    (net (code "47") (name "unconnected-(IC1-CP1-Pad5)") (class "Default")
      (node (ref "IC1") (pin "5") (pinfunction "CP1_5") (pintype "bidirectional"))
    )
    (net (code "48") (name "unconnected-(IC1-CP2-Pad6)") (class "Default")
      (node (ref "IC1") (pin "6") (pinfunction "CP2_6") (pintype "bidirectional"))
    )
    (net (code "49") (name "unconnected-(IC1-EN{slash}NFAULT-Pad14)") (class "Default")
      (node (ref "IC1") (pin "14") (pinfunction "EN/NFAULT_14") (pintype "bidirectional"))
    )
    (net (code "50") (name "unconnected-(IC1-EP-Pad33)") (class "Default")
      (node (ref "IC1") (pin "33") (pinfunction "EP_33") (pintype "bidirectional"))
    )
    (net (code "51") (name "unconnected-(IC1-GND-Pad22)") (class "Default")
      (node (ref "IC1") (pin "22") (pinfunction "GND_22") (pintype "bidirectional"))
    )
    (net (code "52") (name "unconnected-(IC1-GNDPUMP-Pad3)") (class "Default")
      (node (ref "IC1") (pin "3") (pinfunction "GNDPUMP_3") (pintype "bidirectional"))
    )
    (net (code "53") (name "unconnected-(IC1-LSS1_1-Pad1)") (class "Default")
      (node (ref "IC1") (pin "1") (pinfunction "LSS1_1_1") (pintype "bidirectional"))
    )
    (net (code "54") (name "unconnected-(IC1-LSS1_2-Pad2)") (class "Default")
      (node (ref "IC1") (pin "2") (pinfunction "LSS1_2_2") (pintype "bidirectional"))
    )
    (net (code "55") (name "unconnected-(IC1-LSS2_1-Pad23)") (class "Default")
      (node (ref "IC1") (pin "23") (pinfunction "LSS2_1_23") (pintype "bidirectional"))
    )
    (net (code "56") (name "unconnected-(IC1-LSS2_2-Pad24)") (class "Default")
      (node (ref "IC1") (pin "24") (pinfunction "LSS2_2_24") (pintype "bidirectional"))
    )
    (net (code "57") (name "unconnected-(IC1-MODE1-Pad20)") (class "Default")
      (node (ref "IC1") (pin "20") (pinfunction "MODE1_20") (pintype "bidirectional"))
    )
    (net (code "58") (name "unconnected-(IC1-MODE2-Pad19)") (class "Default")
      (node (ref "IC1") (pin "19") (pinfunction "MODE2_19") (pintype "bidirectional"))
    )
    (net (code "59") (name "unconnected-(IC1-MODE3-Pad18)") (class "Default")
      (node (ref "IC1") (pin "18") (pinfunction "MODE3_18") (pintype "bidirectional"))
    )
    (net (code "60") (name "unconnected-(IC1-NSTBY-Pad10)") (class "Default")
      (node (ref "IC1") (pin "10") (pinfunction "NSTBY_10") (pintype "bidirectional"))
    )
    (net (code "61") (name "unconnected-(IC1-OFFSET-Pad9)") (class "Default")
      (node (ref "IC1") (pin "9") (pinfunction "OFFSET_9") (pintype "bidirectional"))
    )
    (net (code "62") (name "unconnected-(IC1-OUT1_1-Pad31)") (class "Default")
      (node (ref "IC1") (pin "31") (pinfunction "OUT1_1_31") (pintype "bidirectional"))
    )
    (net (code "63") (name "unconnected-(IC1-OUT1_2-Pad32)") (class "Default")
      (node (ref "IC1") (pin "32") (pinfunction "OUT1_2_32") (pintype "bidirectional"))
    )
    (net (code "64") (name "unconnected-(IC1-OUT2_1-Pad25)") (class "Default")
      (node (ref "IC1") (pin "25") (pinfunction "OUT2_1_25") (pintype "bidirectional"))
    )
    (net (code "65") (name "unconnected-(IC1-OUT2_2-Pad26)") (class "Default")
      (node (ref "IC1") (pin "26") (pinfunction "OUT2_2_26") (pintype "bidirectional"))
    )
    (net (code "66") (name "unconnected-(IC1-PWM1-Pad11)") (class "Default")
      (node (ref "IC1") (pin "11") (pinfunction "PWM1_11") (pintype "bidirectional"))
    )
    (net (code "67") (name "unconnected-(IC1-PWM2-Pad12)") (class "Default")
      (node (ref "IC1") (pin "12") (pinfunction "PWM2_12") (pintype "bidirectional"))
    )
    (net (code "68") (name "unconnected-(IC1-REF-Pad15)") (class "Default")
      (node (ref "IC1") (pin "15") (pinfunction "REF_15") (pintype "bidirectional"))
    )
    (net (code "69") (name "unconnected-(IC1-SR-Pad21)") (class "Default")
      (node (ref "IC1") (pin "21") (pinfunction "SR_21") (pintype "bidirectional"))
    )
    (net (code "70") (name "unconnected-(IC1-TOFF-Pad16)") (class "Default")
      (node (ref "IC1") (pin "16") (pinfunction "TOFF_16") (pintype "bidirectional"))
    )
    (net (code "71") (name "unconnected-(IC1-V1-Pad8)") (class "Default")
      (node (ref "IC1") (pin "8") (pinfunction "V1_8") (pintype "bidirectional"))
    )
    (net (code "72") (name "unconnected-(IC1-V2-Pad17)") (class "Default")
      (node (ref "IC1") (pin "17") (pinfunction "V2_17") (pintype "bidirectional"))
    )
    (net (code "73") (name "unconnected-(IC1-VBOOT-Pad7)") (class "Default")
      (node (ref "IC1") (pin "7") (pinfunction "VBOOT_7") (pintype "bidirectional"))
    )
    (net (code "74") (name "unconnected-(IC1-VDD-Pad13)") (class "Default")
      (node (ref "IC1") (pin "13") (pinfunction "VDD_13") (pintype "bidirectional"))
    )
    (net (code "75") (name "unconnected-(IC1-VSPUMP-Pad4)") (class "Default")
      (node (ref "IC1") (pin "4") (pinfunction "VSPUMP_4") (pintype "bidirectional"))
    )
    (net (code "76") (name "unconnected-(IC1-VS_1-Pad27)") (class "Default")
      (node (ref "IC1") (pin "27") (pinfunction "VS_1_27") (pintype "bidirectional"))
    )
    (net (code "77") (name "unconnected-(IC1-VS_2-Pad28)") (class "Default")
      (node (ref "IC1") (pin "28") (pinfunction "VS_2_28") (pintype "bidirectional"))
    )
    (net (code "78") (name "unconnected-(IC1-VS_3-Pad29)") (class "Default")
      (node (ref "IC1") (pin "29") (pinfunction "VS_3_29") (pintype "bidirectional"))
    )
    (net (code "79") (name "unconnected-(IC1-VS_4-Pad30)") (class "Default")
      (node (ref "IC1") (pin "30") (pinfunction "VS_4_30") (pintype "bidirectional"))
    )
    (net (code "80") (name "unconnected-(J1-1-Pad8)") (class "Default")
      (node (ref "J1") (pin "8") (pinfunction "1_8") (pintype "passive"))
    )
    (net (code "81") (name "unconnected-(J1-2-Pad7)") (class "Default")
      (node (ref "J1") (pin "7") (pinfunction "2_7") (pintype "passive"))
    )
    (net (code "82") (name "unconnected-(J1-3-Pad6)") (class "Default")
      (node (ref "J1") (pin "6") (pinfunction "3_6") (pintype "passive"))
    )
    (net (code "83") (name "unconnected-(J1-4-Pad5)") (class "Default")
      (node (ref "J1") (pin "5") (pinfunction "4_5") (pintype "passive"))
    )
    (net (code "84") (name "unconnected-(J1-5-Pad4)") (class "Default")
      (node (ref "J1") (pin "4") (pinfunction "5_4") (pintype "passive"))
    )
    (net (code "85") (name "unconnected-(J1-6-Pad3)") (class "Default")
      (node (ref "J1") (pin "3") (pinfunction "6_3") (pintype "passive"))
    )
    (net (code "86") (name "unconnected-(J1-7-Pad2)") (class "Default")
      (node (ref "J1") (pin "2") (pinfunction "7_2") (pintype "passive"))
    )
    (net (code "87") (name "unconnected-(J1-8-Pad1)") (class "Default")
      (node (ref "J1") (pin "1") (pinfunction "8_1") (pintype "passive"))
    )
    (net (code "88") (name "unconnected-(J2-1-Pad8)") (class "Default")
      (node (ref "J2") (pin "8") (pinfunction "1_8") (pintype "passive"))
    )
    (net (code "89") (name "unconnected-(J2-2-Pad7)") (class "Default")
      (node (ref "J2") (pin "7") (pinfunction "2_7") (pintype "passive"))
    )
    (net (code "90") (name "unconnected-(J2-3-Pad6)") (class "Default")
      (node (ref "J2") (pin "6") (pinfunction "3_6") (pintype "passive"))
    )
    (net (code "91") (name "unconnected-(J2-4-Pad5)") (class "Default")
      (node (ref "J2") (pin "5") (pinfunction "4_5") (pintype "passive"))
    )
    (net (code "92") (name "unconnected-(J2-5-Pad4)") (class "Default")
      (node (ref "J2") (pin "4") (pinfunction "5_4") (pintype "passive"))
    )
    (net (code "93") (name "unconnected-(J2-6-Pad3)") (class "Default")
      (node (ref "J2") (pin "3") (pinfunction "6_3") (pintype "passive"))
    )
    (net (code "94") (name "unconnected-(J2-7-Pad2)") (class "Default")
      (node (ref "J2") (pin "2") (pinfunction "7_2") (pintype "passive"))
    )
    (net (code "95") (name "unconnected-(J2-8-Pad1)") (class "Default")
      (node (ref "J2") (pin "1") (pinfunction "8_1") (pintype "passive"))
    )
    (net (code "96") (name "unconnected-(J7-PadRING_SW)") (class "Default")
      (node (ref "J7") (pin "RING_SW") (pinfunction "RING_SW_RING_SW") (pintype "bidirectional"))
    )
  )
)
